# RAFT_DuckLink_LDO_3V3.net
KiCad netlist of a schematic drawn in EAGLE
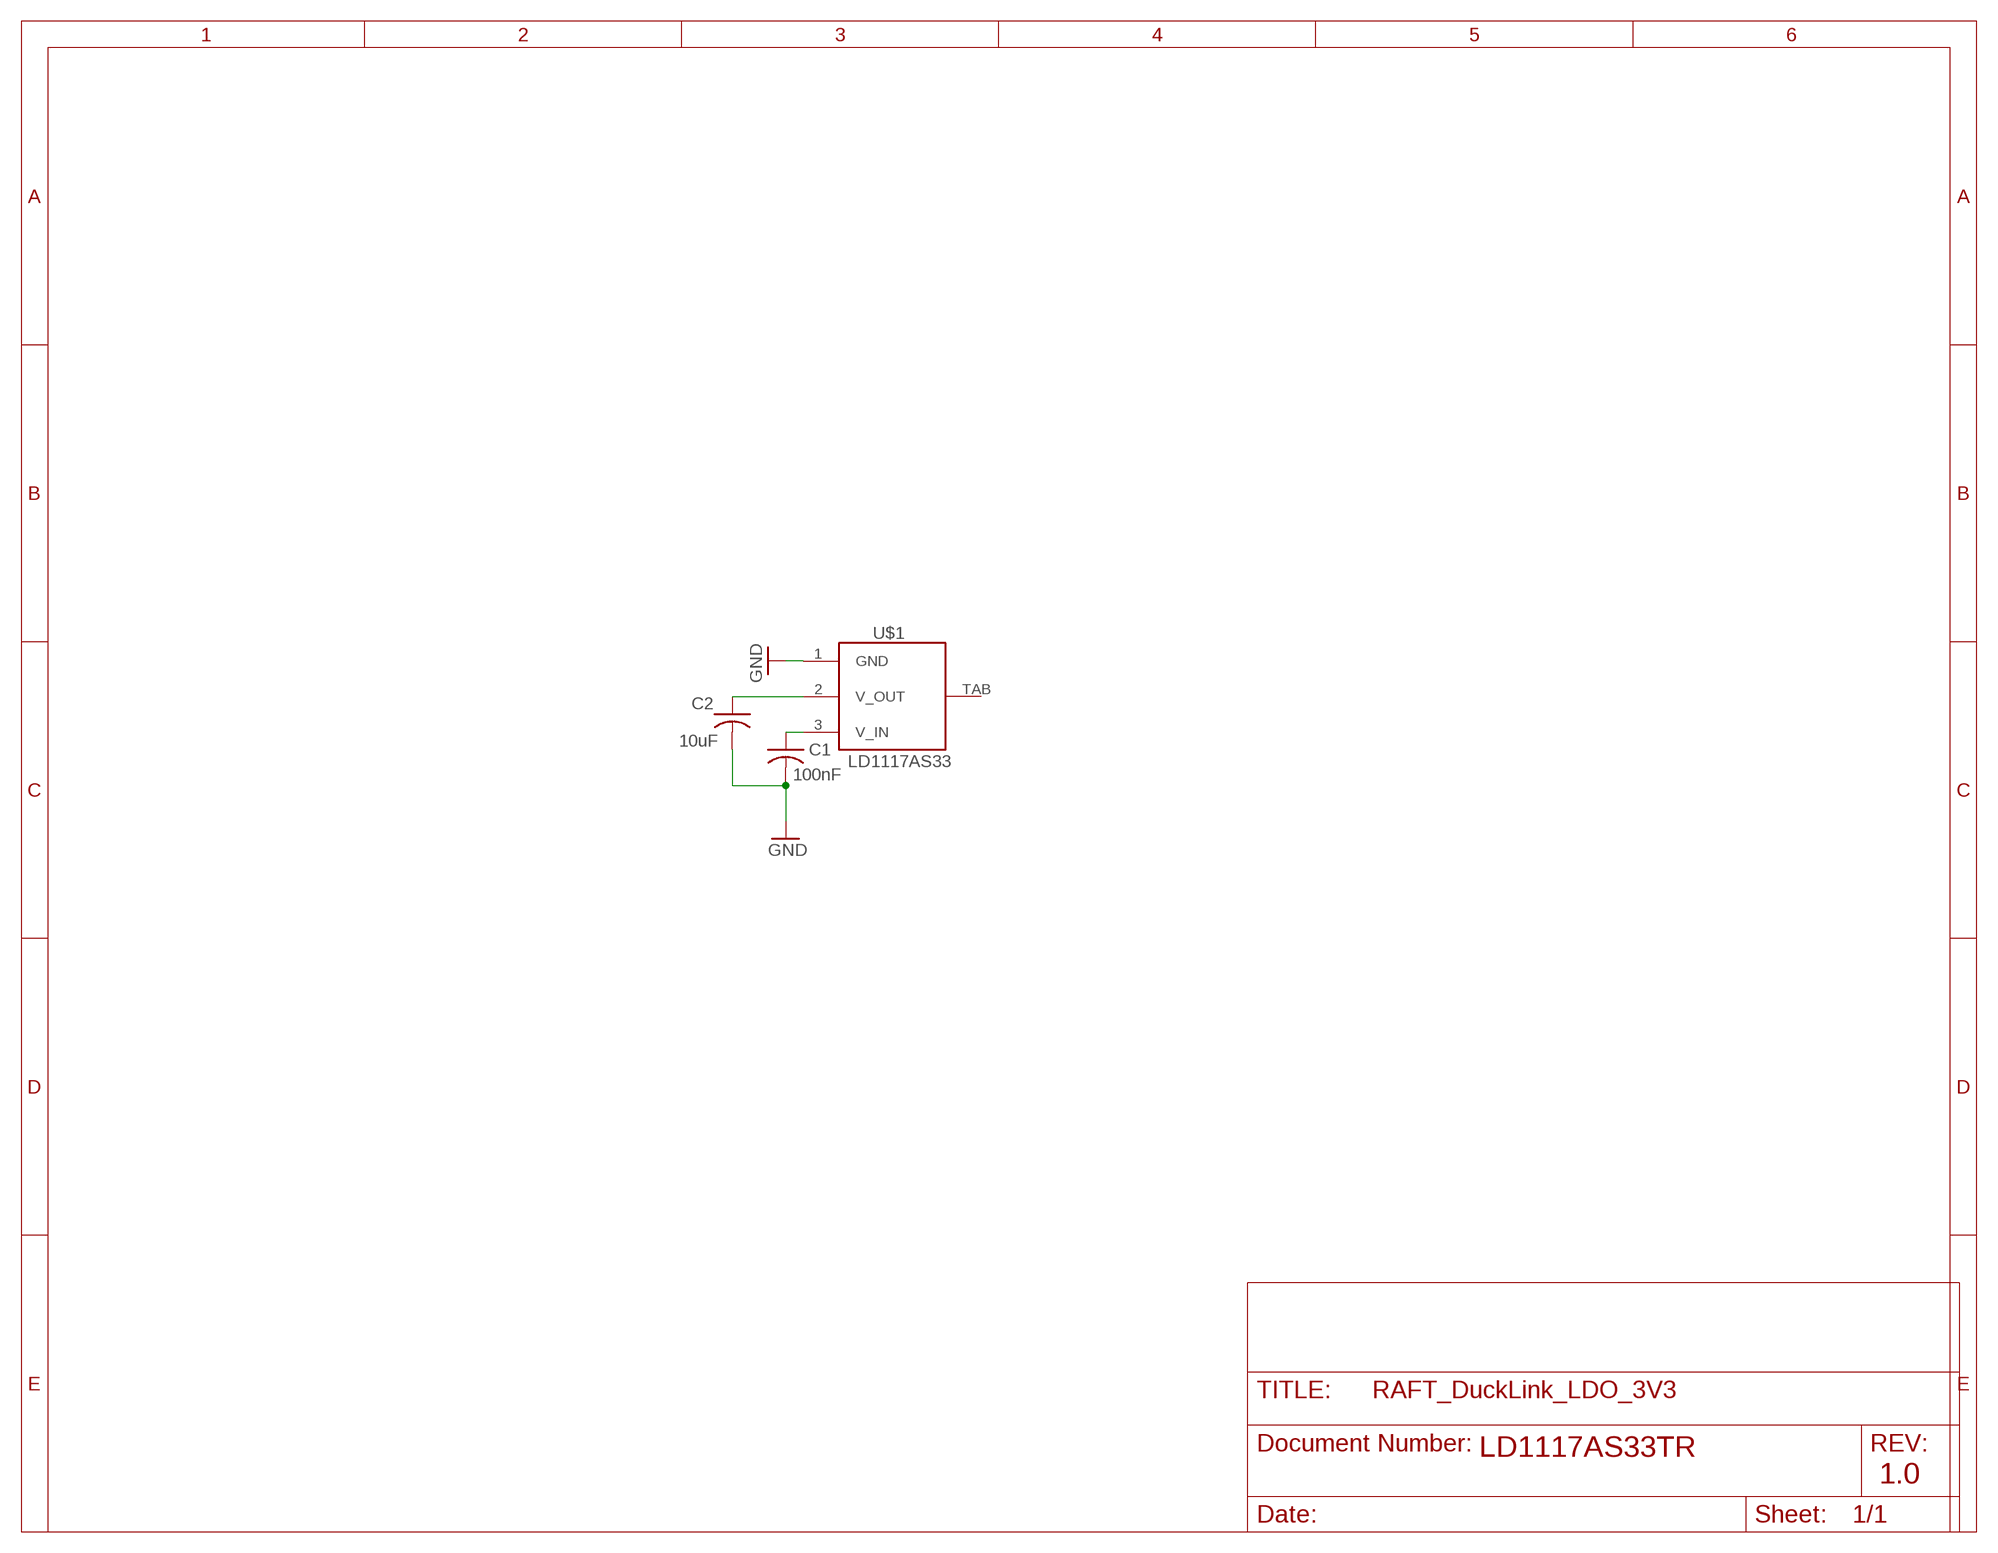
[diagram p0: schematic, sheet 1]

(export (version "E")
  (design (tool "Eeschema 10.0.6"))
  (components
    (comp (ref "C1")
      (value "100nF")
      (footprint "eagle-import:C0402")
      (libsource (lib "eagle-import") (part "C-USC0402"))
    )
    (comp (ref "C2")
      (value "10uF")
      (footprint "eagle-import:C0402")
      (libsource (lib "eagle-import") (part "C-USC0402"))
    )
    (comp (ref "U$1")
      (value "LD1117AS33")
      (footprint "eagle-import:SOT223")
      (fields (field (name "MF") "STMicroelectronics"))
      (libsource (lib "eagle-import") (part "LD1117AS33"))
    )
  )
  (nets
    (net (code "1") (name "GND") (class "Default")
      (node (ref "C1") (pin "2") (pinfunction "2_2") (pintype "passive"))
      (node (ref "C2") (pin "2") (pinfunction "2_2") (pintype "passive"))
      (node (ref "U$1") (pin "1") (pinfunction "GND_1") (pintype "bidirectional"))
    )
    (net (code "2") (name "Net-(U$1-V_IN)") (class "Default")
      (node (ref "C1") (pin "1") (pinfunction "1_1") (pintype "passive"))
      (node (ref "U$1") (pin "3") (pinfunction "V_IN_3") (pintype "bidirectional"))
    )
    (net (code "3") (name "Net-(U$1-V_OUT)") (class "Default")
      (node (ref "C2") (pin "1") (pinfunction "1_1") (pintype "passive"))
      (node (ref "U$1") (pin "2") (pinfunction "V_OUT_2") (pintype "bidirectional"))
    )
    (net (code "4") (name "unconnected-(U$1-PadTAB)") (class "Default")
      (node (ref "U$1") (pin "TAB") (pinfunction "TAB_TAB") (pintype "bidirectional"))
    )
  )
)
